# input_stage_other.net
KiCad netlist of a schematic drawn in EAGLE
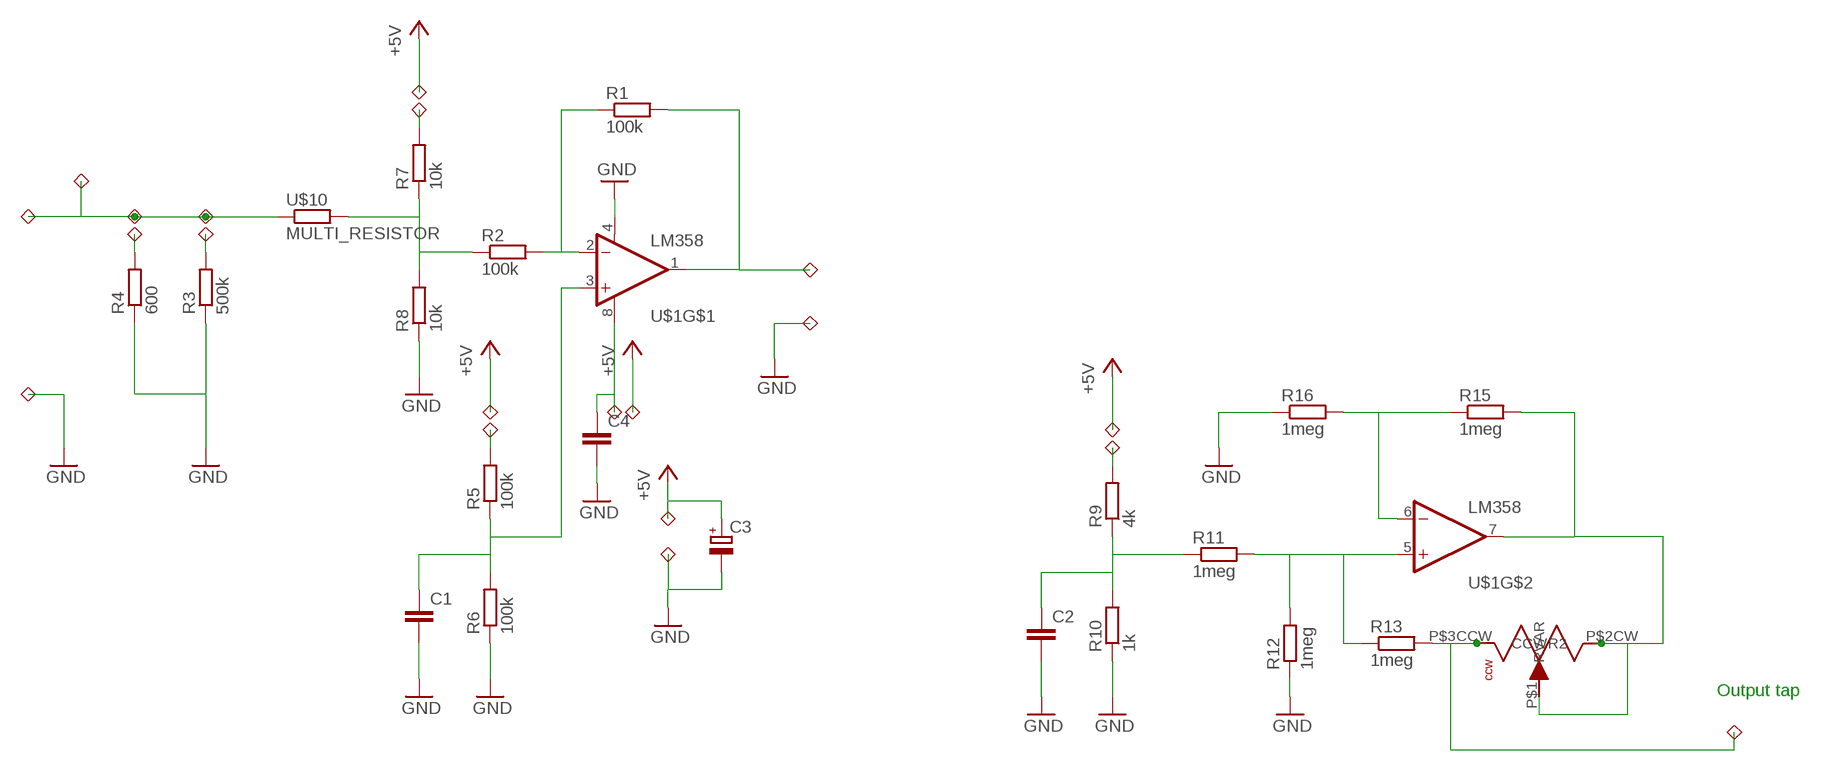
[diagram p0: schematic, sheet 1]

(export (version "E")
  (design (tool "Eeschema 10.0.6"))
  (components
    (comp (ref "C1")
      (value "C-EUC0603")
      (footprint "eagle-import:C0603")
      (libsource (lib "eagle-import") (part "C-EUC0603"))
    )
    (comp (ref "C2")
      (value "C-EUC0603")
      (footprint "eagle-import:C0603")
      (libsource (lib "eagle-import") (part "C-EUC0603"))
    )
    (comp (ref "C3")
      (value "CPOL-EUC/6032-28R")
      (footprint "eagle-import:C_6032-28R")
      (libsource (lib "eagle-import") (part "CPOL-EUC/6032-28R"))
    )
    (comp (ref "C4")
      (value "C-EUC0603")
      (footprint "eagle-import:C0603")
      (libsource (lib "eagle-import") (part "C-EUC0603"))
    )
    (comp (ref "R1")
      (value "100k")
      (footprint "eagle-import:R0603")
      (libsource (lib "eagle-import") (part "R-EU_R0603"))
    )
    (comp (ref "R2")
      (value "100k")
      (footprint "eagle-import:R0603")
      (libsource (lib "eagle-import") (part "R-EU_R0603"))
    )
    (comp (ref "R3")
      (value "500k")
      (footprint "eagle-import:R0603")
      (libsource (lib "eagle-import") (part "R-EU_R0603"))
    )
    (comp (ref "R4")
      (value "600")
      (footprint "eagle-import:R0603")
      (libsource (lib "eagle-import") (part "R-EU_R0603"))
    )
    (comp (ref "R5")
      (value "100k")
      (footprint "eagle-import:R0603")
      (libsource (lib "eagle-import") (part "R-EU_R0603"))
    )
    (comp (ref "R6")
      (value "100k")
      (footprint "eagle-import:R0603")
      (libsource (lib "eagle-import") (part "R-EU_R0603"))
    )
    (comp (ref "R7")
      (value "10k")
      (footprint "eagle-import:R0603")
      (libsource (lib "eagle-import") (part "R-EU_R0603"))
    )
    (comp (ref "R8")
      (value "10k")
      (footprint "eagle-import:R0603")
      (libsource (lib "eagle-import") (part "R-EU_R0603"))
    )
    (comp (ref "R9")
      (value "4k")
      (footprint "eagle-import:R0603")
      (libsource (lib "eagle-import") (part "R-EU_R0603"))
    )
    (comp (ref "R10")
      (value "1k")
      (footprint "eagle-import:R0603")
      (libsource (lib "eagle-import") (part "R-EU_R0603"))
    )
    (comp (ref "R11")
      (value "1meg")
      (footprint "eagle-import:R0603")
      (libsource (lib "eagle-import") (part "R-EU_R0603"))
    )
    (comp (ref "R12")
      (value "1meg")
      (footprint "eagle-import:R0603")
      (libsource (lib "eagle-import") (part "R-EU_R0603"))
    )
    (comp (ref "R13")
      (value "1meg")
      (footprint "eagle-import:R0603")
      (libsource (lib "eagle-import") (part "R-EU_R0603"))
    )
    (comp (ref "R15")
      (value "1meg")
      (footprint "eagle-import:R0603")
      (libsource (lib "eagle-import") (part "R-EU_R0603"))
    )
    (comp (ref "R16")
      (value "1meg")
      (footprint "eagle-import:R0603")
      (libsource (lib "eagle-import") (part "R-EU_R0603"))
    )
    (comp (ref "U$1")
      (value "LM358")
      (footprint "eagle-import:SO08")
      (libsource (lib "eagle-import") (part "LM358"))
    )
    (comp (ref "U$2")
      (value "1PIN")
      (footprint "eagle-import:THUMBNAIL")
      (libsource (lib "eagle-import") (part "1PIN"))
    )
    (comp (ref "U$3")
      (value "1PIN")
      (footprint "eagle-import:THUMBNAIL")
      (libsource (lib "eagle-import") (part "1PIN"))
    )
    (comp (ref "U$4")
      (value "1PIN")
      (footprint "eagle-import:THUMBNAIL")
      (libsource (lib "eagle-import") (part "1PIN"))
    )
    (comp (ref "U$5")
      (value "1PIN")
      (footprint "eagle-import:THUMBNAIL")
      (libsource (lib "eagle-import") (part "1PIN"))
    )
    (comp (ref "U$6")
      (value "1PIN")
      (footprint "eagle-import:THUMBNAIL")
      (libsource (lib "eagle-import") (part "1PIN"))
    )
    (comp (ref "U$7")
      (value "1PIN")
      (footprint "eagle-import:THUMBNAIL")
      (libsource (lib "eagle-import") (part "1PIN"))
    )
    (comp (ref "U$8")
      (value "1PIN")
      (footprint "eagle-import:THUMBNAIL")
      (libsource (lib "eagle-import") (part "1PIN"))
    )
    (comp (ref "U$9")
      (value "1PIN")
      (footprint "eagle-import:THUMBNAIL")
      (libsource (lib "eagle-import") (part "1PIN"))
    )
    (comp (ref "U$10")
      (value "MULTI_RESISTOR")
      (footprint "eagle-import:MULTI_PAD")
      (libsource (lib "eagle-import") (part "MULTI_RESISTOR"))
    )
    (comp (ref "U$11")
      (value "1PIN")
      (footprint "eagle-import:THUMBNAIL")
      (libsource (lib "eagle-import") (part "1PIN"))
    )
    (comp (ref "U$12")
      (value "1PIN")
      (footprint "eagle-import:THUMBNAIL")
      (libsource (lib "eagle-import") (part "1PIN"))
    )
    (comp (ref "U$13")
      (value "1PIN")
      (footprint "eagle-import:THUMBNAIL")
      (libsource (lib "eagle-import") (part "1PIN"))
    )
    (comp (ref "U$14")
      (value "1PIN")
      (footprint "eagle-import:THUMBNAIL")
      (libsource (lib "eagle-import") (part "1PIN"))
    )
    (comp (ref "U$15")
      (value "SMD-POT")
      (footprint "eagle-import:POT_PADS")
      (libsource (lib "eagle-import") (part "SMD-POT"))
    )
    (comp (ref "U$16")
      (value "1PIN_SM")
      (footprint "eagle-import:THUMBNAIL_SM")
      (libsource (lib "eagle-import") (part "1PIN_SM"))
    )
    (comp (ref "U$17")
      (value "1PIN_SM")
      (footprint "eagle-import:THUMBNAIL_SM")
      (libsource (lib "eagle-import") (part "1PIN_SM"))
    )
    (comp (ref "U$18")
      (value "1PIN_SM")
      (footprint "eagle-import:THUMBNAIL_SM")
      (libsource (lib "eagle-import") (part "1PIN_SM"))
    )
    (comp (ref "U$19")
      (value "1PIN_SM")
      (footprint "eagle-import:THUMBNAIL_SM")
      (libsource (lib "eagle-import") (part "1PIN_SM"))
    )
    (comp (ref "U$20")
      (value "1PIN_SM")
      (footprint "eagle-import:THUMBNAIL_SM")
      (libsource (lib "eagle-import") (part "1PIN_SM"))
    )
    (comp (ref "U$21")
      (value "1PIN_SM")
      (footprint "eagle-import:THUMBNAIL_SM")
      (libsource (lib "eagle-import") (part "1PIN_SM"))
    )
    (comp (ref "U$22")
      (value "1PIN_SM")
      (footprint "eagle-import:THUMBNAIL_SM")
      (libsource (lib "eagle-import") (part "1PIN_SM"))
    )
    (comp (ref "U$23")
      (value "1PIN_SM")
      (footprint "eagle-import:THUMBNAIL_SM")
      (libsource (lib "eagle-import") (part "1PIN_SM"))
    )
  )
  (nets
    (net (code "1") (name "+5V") (class "Default")
      (node (ref "C3") (pin "+") (pinfunction "+_+") (pintype "passive"))
      (node (ref "U$17") (pin "P$1") (pinfunction "P$1_P$1") (pintype "bidirectional"))
      (node (ref "U$19") (pin "P$1") (pinfunction "P$1_P$1") (pintype "bidirectional"))
      (node (ref "U$2") (pin "P$1") (pinfunction "P$1_P$1") (pintype "bidirectional"))
      (node (ref "U$21") (pin "P$1") (pinfunction "P$1_P$1") (pintype "bidirectional"))
      (node (ref "U$23") (pin "P$1") (pinfunction "P$1_P$1") (pintype "bidirectional"))
    )
    (net (code "2") (name "GND") (class "Default")
      (node (ref "C1") (pin "2") (pinfunction "2_2") (pintype "passive"))
      (node (ref "C2") (pin "2") (pinfunction "2_2") (pintype "passive"))
      (node (ref "C3") (pin "-") (pinfunction "-_-") (pintype "passive"))
      (node (ref "C4") (pin "2") (pinfunction "2_2") (pintype "passive"))
      (node (ref "R10") (pin "1") (pinfunction "1_1") (pintype "passive"))
      (node (ref "R12") (pin "1") (pinfunction "1_1") (pintype "passive"))
      (node (ref "R16") (pin "1") (pinfunction "1_1") (pintype "passive"))
      (node (ref "R3") (pin "1") (pinfunction "1_1") (pintype "passive"))
      (node (ref "R4") (pin "1") (pinfunction "1_1") (pintype "passive"))
      (node (ref "R6") (pin "1") (pinfunction "1_1") (pintype "passive"))
      (node (ref "R8") (pin "1") (pinfunction "1_1") (pintype "passive"))
      (node (ref "U$1") (pin "4") (pinfunction "V-_4") (pintype "power_in"))
      (node (ref "U$3") (pin "P$1") (pinfunction "P$1_P$1") (pintype "bidirectional"))
      (node (ref "U$8") (pin "P$1") (pinfunction "P$1_P$1") (pintype "bidirectional"))
      (node (ref "U$9") (pin "P$1") (pinfunction "P$1_P$1") (pintype "bidirectional"))
    )
    (net (code "3") (name "Net-(C2-Pad1)") (class "Default")
      (node (ref "C2") (pin "1") (pinfunction "1_1") (pintype "passive"))
      (node (ref "R10") (pin "2") (pinfunction "2_2") (pintype "passive"))
      (node (ref "R11") (pin "1") (pinfunction "1_1") (pintype "passive"))
      (node (ref "R9") (pin "1") (pinfunction "1_1") (pintype "passive"))
    )
    (net (code "4") (name "Net-(R2-Pad1)") (class "Default")
      (node (ref "R2") (pin "1") (pinfunction "1_1") (pintype "passive"))
      (node (ref "R7") (pin "1") (pinfunction "1_1") (pintype "passive"))
      (node (ref "R8") (pin "2") (pinfunction "2_2") (pintype "passive"))
      (node (ref "U$10") (pin "2") (pinfunction "2_2") (pintype "passive"))
    )
    (net (code "5") (name "Net-(R3-Pad2)") (class "Default")
      (node (ref "R3") (pin "2") (pinfunction "2_2") (pintype "passive"))
      (node (ref "U$11") (pin "P$1") (pinfunction "P$1_P$1") (pintype "bidirectional"))
    )
    (net (code "6") (name "Net-(R4-Pad2)") (class "Default")
      (node (ref "R4") (pin "2") (pinfunction "2_2") (pintype "passive"))
      (node (ref "U$7") (pin "P$1") (pinfunction "P$1_P$1") (pintype "bidirectional"))
    )
    (net (code "7") (name "Net-(R5-Pad2)") (class "Default")
      (node (ref "R5") (pin "2") (pinfunction "2_2") (pintype "passive"))
      (node (ref "U$20") (pin "P$1") (pinfunction "P$1_P$1") (pintype "bidirectional"))
    )
    (net (code "8") (name "Net-(R7-Pad2)") (class "Default")
      (node (ref "R7") (pin "2") (pinfunction "2_2") (pintype "passive"))
      (node (ref "U$18") (pin "P$1") (pinfunction "P$1_P$1") (pintype "bidirectional"))
    )
    (net (code "9") (name "Net-(R9-Pad2)") (class "Default")
      (node (ref "R9") (pin "2") (pinfunction "2_2") (pintype "passive"))
      (node (ref "U$16") (pin "P$1") (pinfunction "P$1_P$1") (pintype "bidirectional"))
    )
    (net (code "10") (name "Net-(U$1A-+IN)") (class "Default")
      (node (ref "C1") (pin "1") (pinfunction "1_1") (pintype "passive"))
      (node (ref "R5") (pin "1") (pinfunction "1_1") (pintype "passive"))
      (node (ref "R6") (pin "2") (pinfunction "2_2") (pintype "passive"))
      (node (ref "U$1") (pin "3") (pinfunction "+IN_3") (pintype "input"))
    )
    (net (code "11") (name "Net-(U$1A--IN)") (class "Default")
      (node (ref "R1") (pin "1") (pinfunction "1_1") (pintype "passive"))
      (node (ref "R2") (pin "2") (pinfunction "2_2") (pintype "passive"))
      (node (ref "U$1") (pin "2") (pinfunction "-IN_2") (pintype "input"))
    )
    (net (code "12") (name "Net-(U$1A-OUT)") (class "Default")
      (node (ref "R1") (pin "2") (pinfunction "2_2") (pintype "passive"))
      (node (ref "U$1") (pin "1") (pinfunction "OUT_1") (pintype "output"))
      (node (ref "U$4") (pin "P$1") (pinfunction "P$1_P$1") (pintype "bidirectional"))
    )
    (net (code "13") (name "Net-(U$1A-V+)") (class "Default")
      (node (ref "C4") (pin "1") (pinfunction "1_1") (pintype "passive"))
      (node (ref "U$1") (pin "8") (pinfunction "V+_8") (pintype "power_in"))
      (node (ref "U$22") (pin "P$1") (pinfunction "P$1_P$1") (pintype "bidirectional"))
    )
    (net (code "14") (name "Net-(U$1B-+IN)") (class "Default")
      (node (ref "R11") (pin "2") (pinfunction "2_2") (pintype "passive"))
      (node (ref "R12") (pin "2") (pinfunction "2_2") (pintype "passive"))
      (node (ref "R13") (pin "1") (pinfunction "1_1") (pintype "passive"))
      (node (ref "U$1") (pin "5") (pinfunction "+IN_5") (pintype "input"))
    )
    (net (code "15") (name "Net-(U$1B--IN)") (class "Default")
      (node (ref "R15") (pin "1") (pinfunction "1_1") (pintype "passive"))
      (node (ref "R16") (pin "2") (pinfunction "2_2") (pintype "passive"))
      (node (ref "U$1") (pin "6") (pinfunction "-IN_6") (pintype "input"))
    )
    (net (code "16") (name "Net-(U$10-Pad1)") (class "Default")
      (node (ref "U$10") (pin "1") (pinfunction "1_1") (pintype "passive"))
      (node (ref "U$12") (pin "P$1") (pinfunction "P$1_P$1") (pintype "bidirectional"))
      (node (ref "U$13") (pin "P$1") (pinfunction "P$1_P$1") (pintype "bidirectional"))
      (node (ref "U$5") (pin "P$1") (pinfunction "P$1_P$1") (pintype "bidirectional"))
      (node (ref "U$6") (pin "P$1") (pinfunction "P$1_P$1") (pintype "bidirectional"))
    )
    (net (code "17") (name "Net-(U$15-CCW)") (class "Default")
      (node (ref "R13") (pin "2") (pinfunction "2_2") (pintype "passive"))
      (node (ref "U$14") (pin "P$1") (pinfunction "P$1_P$1") (pintype "bidirectional"))
      (node (ref "U$15") (pin "P$3CCW") (pinfunction "CCW_P$3CCW") (pintype "bidirectional"))
    )
    (net (code "18") (name "Net-(U$15-R2)") (class "Default")
      (node (ref "R15") (pin "2") (pinfunction "2_2") (pintype "passive"))
      (node (ref "U$1") (pin "7") (pinfunction "OUT_7") (pintype "output"))
      (node (ref "U$15") (pin "P$1") (pinfunction "RVAR_P$1") (pintype "bidirectional"))
      (node (ref "U$15") (pin "P$2CW") (pinfunction "R2_P$2CW") (pintype "bidirectional"))
    )
  )
)
